# CPU_GPIOA_F.net
KiCad netlist of a schematic drawn in Altium Designer
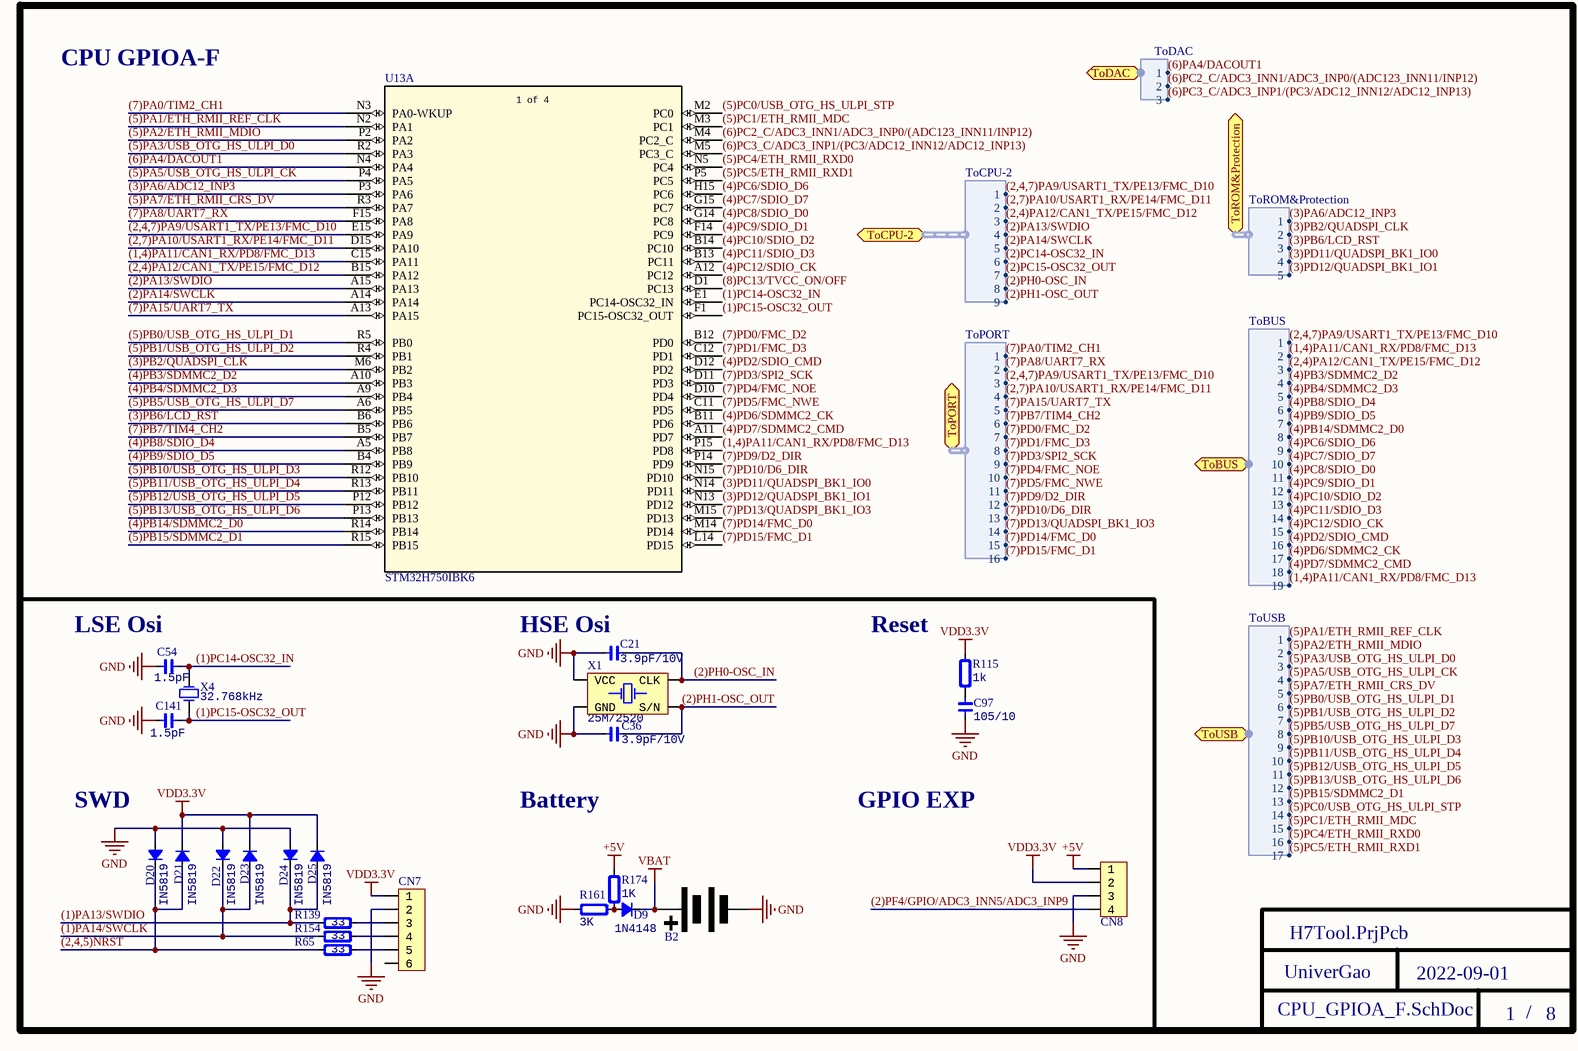
[diagram p0: CPU_GPIOA_F.SchDoc]

(export (version "E")
  (design (tool "Eeschema 10.0.6"))
  (components
    (comp (ref "B2")
      (value "Battery")
      (footprint "PCB_Battery:CR2032-1")
      (libsource (lib "SCH_Battery") (part "Battery"))
    )
    (comp (ref "C21")
      (value "3.9pF/10V")
      (footprint "PCB_PassiveCap:CAP_0603")
      (description "Capacitor")
      (fields (field (name "Comment") "C0603"))
      (libsource (lib "SCH_Passive") (part "Cap_0603"))
    )
    (comp (ref "C36")
      (value "3.9pF/10V")
      (footprint "PCB_PassiveCap:CAP_0603")
      (description "Capacitor")
      (fields (field (name "Comment") "C0603"))
      (libsource (lib "SCH_Passive") (part "Cap_0603"))
    )
    (comp (ref "C54")
      (value "1.5pF")
      (footprint "PCB_PassiveCap:CAP_0603")
      (description "Capacitor")
      (fields (field (name "Comment") "C0603"))
      (libsource (lib "SCH_Passive") (part "Cap_0603"))
    )
    (comp (ref "C97")
      (value "105/10")
      (footprint "PCB_PassiveCap:CAP_0603")
      (description "Capacitor")
      (fields (field (name "Comment") "C0603"))
      (libsource (lib "") (part "Cap_0603_1"))
    )
    (comp (ref "C141")
      (value "1.5pF")
      (footprint "PCB_PassiveCap:CAP_0603")
      (description "Capacitor")
      (fields (field (name "Comment") "C0603"))
      (libsource (lib "SCH_Passive") (part "Cap_0603"))
    )
    (comp (ref "CN7")
      (value "HDR1x6")
      (footprint "PCB_ConnectorHDR:HDR1X6_1.27_180")
      (description "Header")
      (libsource (lib "SCH_ConnectorHDR") (part "HDR1x6_1.27"))
    )
    (comp (ref "CN8")
      (value "HDR1x4")
      (footprint "PCB_ConnectorHDR:HDR1X4_1.27_180")
      (description "Header")
      (libsource (lib "SCH_ConnectorHDR") (part "HDR1x4_1.27"))
    )
    (comp (ref "D9")
      (value "1N4148")
      (footprint "PCB_ActiveDIO:DO-214AC")
      (description "Diode")
      (libsource (lib "SCH_Active") (part "Diode_SMA"))
    )
    (comp (ref "D20")
      (value "~")
      (footprint "PCB_ActiveDIO:SOD-323")
      (description "Diode")
      (fields (field (name "IN5819") "IN5819"))
      (libsource (lib "SCH_Active") (part "Diode_SOD323"))
    )
    (comp (ref "D21")
      (value "~")
      (footprint "PCB_ActiveDIO:SOD-323")
      (description "Diode")
      (fields (field (name "IN5819") "IN5819"))
      (libsource (lib "SCH_Active") (part "Diode_SOD323"))
    )
    (comp (ref "D22")
      (value "~")
      (footprint "PCB_ActiveDIO:SOD-323")
      (description "Diode")
      (fields (field (name "IN5819") "IN5819"))
      (libsource (lib "SCH_Active") (part "Diode_SOD323"))
    )
    (comp (ref "D23")
      (value "~")
      (footprint "PCB_ActiveDIO:SOD-323")
      (description "Diode")
      (fields (field (name "IN5819") "IN5819"))
      (libsource (lib "SCH_Active") (part "Diode_SOD323"))
    )
    (comp (ref "D24")
      (value "~")
      (footprint "PCB_ActiveDIO:SOD-323")
      (description "Diode")
      (fields (field (name "IN5819") "IN5819"))
      (libsource (lib "SCH_Active") (part "Diode_SOD323"))
    )
    (comp (ref "D25")
      (value "~")
      (footprint "PCB_ActiveDIO:SOD-323")
      (description "Diode")
      (fields (field (name "IN5819") "IN5819"))
      (libsource (lib "SCH_Active") (part "Diode_SOD323"))
    )
    (comp (ref "R65")
      (value "33")
      (footprint "PCB_PassiveRes:RES_0603")
      (description "Resistor")
      (fields (field (name "Comment") "R0603"))
      (libsource (lib "SCH_Passive") (part "Res_0603"))
    )
    (comp (ref "R115")
      (value "1k")
      (footprint "PCB_PassiveRes:RES_0603")
      (description "Resistor")
      (fields (field (name "Comment") "R0603"))
      (libsource (lib "SCH_Passive") (part "Res_0603"))
    )
    (comp (ref "R139")
      (value "33")
      (footprint "PCB_PassiveRes:RES_0603")
      (description "Resistor")
      (fields (field (name "Comment") "R0603"))
      (libsource (lib "SCH_Passive") (part "Res_0603"))
    )
    (comp (ref "R154")
      (value "33")
      (footprint "PCB_PassiveRes:RES_0603")
      (description "Resistor")
      (fields (field (name "Comment") "R0603"))
      (libsource (lib "SCH_Passive") (part "Res_0603"))
    )
    (comp (ref "R161")
      (value "3K")
      (footprint "PCB_PassiveRes:RES_0603")
      (description "Resistor")
      (fields (field (name "Comment") "R0603"))
      (libsource (lib "SCH_Passive") (part "Res_0603"))
    )
    (comp (ref "R174")
      (value "1K")
      (footprint "PCB_PassiveRes:RES_0603")
      (description "Resistor")
      (fields (field (name "Comment") "R0603"))
      (libsource (lib "SCH_Passive") (part "Res_0603"))
    )
    (comp (ref "U13")
      (value "STM32H750IBK6")
      (footprint "UFBGA 10X10 P 0.65 176+25")
      (description "No Description Available")
      (fields (field (name "COPYRIGHT") "Copyright (C) 2022 Ultra Librarian. All rights reserved."))
      (libsource (lib "STM32H750IBK6") (part "STM32H750IBK6"))
    )
    (comp (ref "X1")
      (value "25M/2520")
      (footprint "PCB_Oscillator:XT_2520_4")
      (description "Crystal Oscillator")
      (fields (field (name "Comment") "OSC2520"))
      (libsource (lib "SCH_Oscillator") (part "OSC_2520_4P"))
    )
    (comp (ref "X4")
      (value "32.768kHz")
      (footprint "PCB_Oscillator:XT_2012_2")
      (description "Crystal Oscillator")
      (fields (field (name "Comment") "XTAL2012"))
      (libsource (lib "SCH_Oscillator") (part "XTAL_32.768k_2P"))
    )
  )
  (nets
    (net (code "7") (name "+5V") (class "Default")
      (node (ref "CN8") (pin "1") (pinfunction "1_1") (pintype "passive"))
      (node (ref "R174") (pin "2") (pinfunction "2_2") (pintype "passive"))
    )
    (net (code "8") (name "/(1)PA13{slash}SWDIO") (class "Default")
      (node (ref "D24") (pin "2") (pinfunction "K_2") (pintype "passive"))
      (node (ref "D25") (pin "1") (pinfunction "A_1") (pintype "passive"))
      (node (ref "R139") (pin "1") (pinfunction "1_1") (pintype "passive"))
    )
    (net (code "9") (name "/(1)PA14{slash}SWCLK") (class "Default")
      (node (ref "D22") (pin "2") (pinfunction "K_2") (pintype "passive"))
      (node (ref "D23") (pin "1") (pinfunction "A_1") (pintype "passive"))
      (node (ref "R154") (pin "1") (pinfunction "1_1") (pintype "passive"))
    )
    (net (code "10") (name "/(1)PC14-OSC32_IN") (class "Default")
      (node (ref "C54") (pin "2") (pinfunction "2_2") (pintype "passive"))
      (node (ref "U13") (pin "E1") (pinfunction "PC14-OSC32_IN_E1") (pintype "bidirectional"))
      (node (ref "X4") (pin "2") (pinfunction "OSC2_2") (pintype "passive"))
    )
    (net (code "11") (name "/(1)PC15-OSC32_OUT") (class "Default")
      (node (ref "C141") (pin "2") (pinfunction "2_2") (pintype "passive"))
      (node (ref "U13") (pin "F1") (pinfunction "PC15-OSC32_OUT_F1") (pintype "bidirectional"))
      (node (ref "X4") (pin "1") (pinfunction "OSC1_1") (pintype "passive"))
    )
    (net (code "12") (name "/(1,4)PA11{slash}CAN1_RX{slash}PD8{slash}FMC_D13") (class "Default")
      (node (ref "U13") (pin "C15") (pinfunction "PA11_C15") (pintype "bidirectional"))
      (node (ref "U13") (pin "P15") (pinfunction "PD8_P15") (pintype "bidirectional"))
    )
    (net (code "13") (name "/(2)PA13{slash}SWDIO") (class "Default")
      (node (ref "U13") (pin "A15") (pinfunction "PA13_A15") (pintype "bidirectional"))
    )
    (net (code "14") (name "/(2)PA14{slash}SWCLK") (class "Default")
      (node (ref "U13") (pin "A14") (pinfunction "PA14_A14") (pintype "bidirectional"))
    )
    (net (code "17") (name "/(2)PF4{slash}GPIO{slash}ADC3_INN5{slash}ADC3_INP9") (class "Default")
      (node (ref "CN8") (pin "4") (pinfunction "4_4") (pintype "passive"))
    )
    (net (code "18") (name "/(2)PH0-OSC_IN") (class "Default")
      (node (ref "C21") (pin "2") (pinfunction "2_2") (pintype "passive"))
      (node (ref "X1") (pin "3") (pinfunction "CLK_3") (pintype "passive"))
    )
    (net (code "19") (name "/(2)PH1-OSC_OUT") (class "Default")
      (node (ref "C36") (pin "2") (pinfunction "2_2") (pintype "passive"))
      (node (ref "X1") (pin "1") (pinfunction "S/N_1") (pintype "passive"))
    )
    (net (code "20") (name "/(2,4)PA12{slash}CAN1_TX{slash}PE15{slash}FMC_D12") (class "Default")
      (node (ref "U13") (pin "B15") (pinfunction "PA12_B15") (pintype "bidirectional"))
    )
    (net (code "21") (name "/(2,4,5)NRST") (class "Default")
      (node (ref "D20") (pin "2") (pinfunction "K_2") (pintype "passive"))
      (node (ref "D21") (pin "1") (pinfunction "A_1") (pintype "passive"))
      (node (ref "R65") (pin "1") (pinfunction "1_1") (pintype "passive"))
    )
    (net (code "22") (name "/(2,4,7)PA9{slash}USART1_TX{slash}PE13{slash}FMC_D10") (class "Default")
      (node (ref "U13") (pin "E15") (pinfunction "PA9_E15") (pintype "bidirectional"))
    )
    (net (code "23") (name "/(2,7)PA10{slash}USART1_RX{slash}PE14{slash}FMC_D11") (class "Default")
      (node (ref "U13") (pin "D15") (pinfunction "PA10_D15") (pintype "bidirectional"))
    )
    (net (code "24") (name "/(3)PA6{slash}ADC12_INP3") (class "Default")
      (node (ref "U13") (pin "P3") (pinfunction "PA6_P3") (pintype "bidirectional"))
    )
    (net (code "25") (name "/(3)PB2{slash}QUADSPI_CLK") (class "Default")
      (node (ref "U13") (pin "M6") (pinfunction "PB2_M6") (pintype "bidirectional"))
    )
    (net (code "26") (name "/(3)PB6{slash}LCD_RST") (class "Default")
      (node (ref "U13") (pin "B6") (pinfunction "PB6_B6") (pintype "bidirectional"))
    )
    (net (code "27") (name "/(3)PD11{slash}QUADSPI_BK1_IO0") (class "Default")
      (node (ref "U13") (pin "N14") (pinfunction "PD11_N14") (pintype "bidirectional"))
    )
    (net (code "28") (name "/(3)PD12{slash}QUADSPI_BK1_IO1") (class "Default")
      (node (ref "U13") (pin "N13") (pinfunction "PD12_N13") (pintype "bidirectional"))
    )
    (net (code "29") (name "/(4)PB3{slash}SDMMC2_D2") (class "Default")
      (node (ref "U13") (pin "A10") (pinfunction "PB3_A10") (pintype "bidirectional"))
    )
    (net (code "30") (name "/(4)PB4{slash}SDMMC2_D3") (class "Default")
      (node (ref "U13") (pin "A9") (pinfunction "PB4_A9") (pintype "bidirectional"))
    )
    (net (code "31") (name "/(4)PB8{slash}SDIO_D4") (class "Default")
      (node (ref "U13") (pin "A5") (pinfunction "PB8_A5") (pintype "bidirectional"))
    )
    (net (code "32") (name "/(4)PB9{slash}SDIO_D5") (class "Default")
      (node (ref "U13") (pin "B4") (pinfunction "PB9_B4") (pintype "bidirectional"))
    )
    (net (code "33") (name "/(4)PB14{slash}SDMMC2_D0") (class "Default")
      (node (ref "U13") (pin "R14") (pinfunction "PB14_R14") (pintype "bidirectional"))
    )
    (net (code "34") (name "/(4)PC6{slash}SDIO_D6") (class "Default")
      (node (ref "U13") (pin "H15") (pinfunction "PC6_H15") (pintype "bidirectional"))
    )
    (net (code "35") (name "/(4)PC7{slash}SDIO_D7") (class "Default")
      (node (ref "U13") (pin "G15") (pinfunction "PC7_G15") (pintype "bidirectional"))
    )
    (net (code "36") (name "/(4)PC8{slash}SDIO_D0") (class "Default")
      (node (ref "U13") (pin "G14") (pinfunction "PC8_G14") (pintype "bidirectional"))
    )
    (net (code "37") (name "/(4)PC9{slash}SDIO_D1") (class "Default")
      (node (ref "U13") (pin "F14") (pinfunction "PC9_F14") (pintype "bidirectional"))
    )
    (net (code "38") (name "/(4)PC10{slash}SDIO_D2") (class "Default")
      (node (ref "U13") (pin "B14") (pinfunction "PC10_B14") (pintype "bidirectional"))
    )
    (net (code "39") (name "/(4)PC11{slash}SDIO_D3") (class "Default")
      (node (ref "U13") (pin "B13") (pinfunction "PC11_B13") (pintype "bidirectional"))
    )
    (net (code "40") (name "/(4)PC12{slash}SDIO_CK") (class "Default")
      (node (ref "U13") (pin "A12") (pinfunction "PC12_A12") (pintype "bidirectional"))
    )
    (net (code "41") (name "/(4)PD2{slash}SDIO_CMD") (class "Default")
      (node (ref "U13") (pin "D12") (pinfunction "PD2_D12") (pintype "bidirectional"))
    )
    (net (code "42") (name "/(4)PD6{slash}SDMMC2_CK") (class "Default")
      (node (ref "U13") (pin "B11") (pinfunction "PD6_B11") (pintype "bidirectional"))
    )
    (net (code "43") (name "/(4)PD7{slash}SDMMC2_CMD") (class "Default")
      (node (ref "U13") (pin "A11") (pinfunction "PD7_A11") (pintype "bidirectional"))
    )
    (net (code "44") (name "/(5)PA1{slash}ETH_RMII_REF_CLK") (class "Default")
      (node (ref "U13") (pin "N2") (pinfunction "PA1_N2") (pintype "bidirectional"))
    )
    (net (code "45") (name "/(5)PA2{slash}ETH_RMII_MDIO") (class "Default")
      (node (ref "U13") (pin "P2") (pinfunction "PA2_P2") (pintype "bidirectional"))
    )
    (net (code "46") (name "/(5)PA3{slash}USB_OTG_HS_ULPI_D0") (class "Default")
      (node (ref "U13") (pin "R2") (pinfunction "PA3_R2") (pintype "bidirectional"))
    )
    (net (code "47") (name "/(5)PA5{slash}USB_OTG_HS_ULPI_CK") (class "Default")
      (node (ref "U13") (pin "P4") (pinfunction "PA5_P4") (pintype "bidirectional"))
    )
    (net (code "48") (name "/(5)PA7{slash}ETH_RMII_CRS_DV") (class "Default")
      (node (ref "U13") (pin "R3") (pinfunction "PA7_R3") (pintype "bidirectional"))
    )
    (net (code "49") (name "/(5)PB0{slash}USB_OTG_HS_ULPI_D1") (class "Default")
      (node (ref "U13") (pin "R5") (pinfunction "PB0_R5") (pintype "bidirectional"))
    )
    (net (code "50") (name "/(5)PB1{slash}USB_OTG_HS_ULPI_D2") (class "Default")
      (node (ref "U13") (pin "R4") (pinfunction "PB1_R4") (pintype "bidirectional"))
    )
    (net (code "51") (name "/(5)PB5{slash}USB_OTG_HS_ULPI_D7") (class "Default")
      (node (ref "U13") (pin "A6") (pinfunction "PB5_A6") (pintype "bidirectional"))
    )
    (net (code "52") (name "/(5)PB10{slash}USB_OTG_HS_ULPI_D3") (class "Default")
      (node (ref "U13") (pin "R12") (pinfunction "PB10_R12") (pintype "bidirectional"))
    )
    (net (code "53") (name "/(5)PB11{slash}USB_OTG_HS_ULPI_D4") (class "Default")
      (node (ref "U13") (pin "R13") (pinfunction "PB11_R13") (pintype "bidirectional"))
    )
    (net (code "54") (name "/(5)PB12{slash}USB_OTG_HS_ULPI_D5") (class "Default")
      (node (ref "U13") (pin "P12") (pinfunction "PB12_P12") (pintype "bidirectional"))
    )
    (net (code "55") (name "/(5)PB13{slash}USB_OTG_HS_ULPI_D6") (class "Default")
      (node (ref "U13") (pin "P13") (pinfunction "PB13_P13") (pintype "bidirectional"))
    )
    (net (code "56") (name "/(5)PB15{slash}SDMMC2_D1") (class "Default")
      (node (ref "U13") (pin "R15") (pinfunction "PB15_R15") (pintype "bidirectional"))
    )
    (net (code "57") (name "/(5)PC0{slash}USB_OTG_HS_ULPI_STP") (class "Default")
      (node (ref "U13") (pin "M2") (pinfunction "PC0_M2") (pintype "bidirectional"))
    )
    (net (code "58") (name "/(5)PC1{slash}ETH_RMII_MDC") (class "Default")
      (node (ref "U13") (pin "M3") (pinfunction "PC1_M3") (pintype "bidirectional"))
    )
    (net (code "59") (name "/(5)PC4{slash}ETH_RMII_RXD0") (class "Default")
      (node (ref "U13") (pin "N5") (pinfunction "PC4_N5") (pintype "bidirectional"))
    )
    (net (code "60") (name "/(5)PC5{slash}ETH_RMII_RXD1") (class "Default")
      (node (ref "U13") (pin "P5") (pinfunction "PC5_P5") (pintype "bidirectional"))
    )
    (net (code "61") (name "/(6)PA4{slash}DACOUT1") (class "Default")
      (node (ref "U13") (pin "N4") (pinfunction "PA4_N4") (pintype "bidirectional"))
    )
    (net (code "62") (name "/(6)PC2_C{slash}ADC3_INN1{slash}ADC3_INP0{slash}(ADC123_INN11{slash}INP12)") (class "Default")
      (node (ref "U13") (pin "M4") (pinfunction "PC2_C_M4") (pintype "bidirectional"))
    )
    (net (code "63") (name "/(6)PC3_C{slash}ADC3_INP1{slash}(PC3{slash}ADC12_INN12{slash}ADC12_INP13)") (class "Default")
      (node (ref "U13") (pin "M5") (pinfunction "PC3_C_M5") (pintype "bidirectional"))
    )
    (net (code "64") (name "/(7)PA0{slash}TIM2_CH1") (class "Default")
      (node (ref "U13") (pin "N3") (pinfunction "PA0-WKUP_N3") (pintype "bidirectional"))
    )
    (net (code "65") (name "/(7)PA8{slash}UART7_RX") (class "Default")
      (node (ref "U13") (pin "F15") (pinfunction "PA8_F15") (pintype "bidirectional"))
    )
    (net (code "66") (name "/(7)PA15{slash}UART7_TX") (class "Default")
      (node (ref "U13") (pin "A13") (pinfunction "PA15_A13") (pintype "bidirectional"))
    )
    (net (code "67") (name "/(7)PB7{slash}TIM4_CH2") (class "Default")
      (node (ref "U13") (pin "B5") (pinfunction "PB7_B5") (pintype "bidirectional"))
    )
    (net (code "68") (name "/(7)PD0{slash}FMC_D2") (class "Default")
      (node (ref "U13") (pin "B12") (pinfunction "PD0_B12") (pintype "bidirectional"))
    )
    (net (code "69") (name "/(7)PD1{slash}FMC_D3") (class "Default")
      (node (ref "U13") (pin "C12") (pinfunction "PD1_C12") (pintype "bidirectional"))
    )
    (net (code "70") (name "/(7)PD3{slash}SPI2_SCK") (class "Default")
      (node (ref "U13") (pin "D11") (pinfunction "PD3_D11") (pintype "bidirectional"))
    )
    (net (code "71") (name "/(7)PD4{slash}FMC_NOE") (class "Default")
      (node (ref "U13") (pin "D10") (pinfunction "PD4_D10") (pintype "bidirectional"))
    )
    (net (code "72") (name "/(7)PD5{slash}FMC_NWE") (class "Default")
      (node (ref "U13") (pin "C11") (pinfunction "PD5_C11") (pintype "bidirectional"))
    )
    (net (code "73") (name "/(7)PD9{slash}D2_DIR") (class "Default")
      (node (ref "U13") (pin "P14") (pinfunction "PD9_P14") (pintype "bidirectional"))
    )
    (net (code "74") (name "/(7)PD10{slash}D6_DIR") (class "Default")
      (node (ref "U13") (pin "N15") (pinfunction "PD10_N15") (pintype "bidirectional"))
    )
    (net (code "75") (name "/(7)PD13{slash}QUADSPI_BK1_IO3") (class "Default")
      (node (ref "U13") (pin "M15") (pinfunction "PD13_M15") (pintype "bidirectional"))
    )
    (net (code "76") (name "/(7)PD14{slash}FMC_D0") (class "Default")
      (node (ref "U13") (pin "M14") (pinfunction "PD14_M14") (pintype "bidirectional"))
    )
    (net (code "77") (name "/(7)PD15{slash}FMC_D1") (class "Default")
      (node (ref "U13") (pin "L14") (pinfunction "PD15_L14") (pintype "bidirectional"))
    )
    (net (code "78") (name "/(8)PC13{slash}TVCC_ON{slash}OFF") (class "Default")
      (node (ref "U13") (pin "D1") (pinfunction "PC13_D1") (pintype "bidirectional"))
    )
    (net (code "85") (name "GND") (class "Default")
      (node (ref "B2") (pin "1") (pinfunction "-_1") (pintype "passive"))
      (node (ref "C141") (pin "1") (pinfunction "1_1") (pintype "passive"))
      (node (ref "C21") (pin "1") (pinfunction "1_1") (pintype "passive"))
      (node (ref "C36") (pin "1") (pinfunction "1_1") (pintype "passive"))
      (node (ref "C54") (pin "1") (pinfunction "1_1") (pintype "passive"))
      (node (ref "C97") (pin "1") (pinfunction "1_1") (pintype "passive"))
      (node (ref "CN7") (pin "2") (pinfunction "2_2") (pintype "passive"))
      (node (ref "CN8") (pin "3") (pinfunction "3_3") (pintype "passive"))
      (node (ref "D20") (pin "1") (pinfunction "A_1") (pintype "passive"))
      (node (ref "D22") (pin "1") (pinfunction "A_1") (pintype "passive"))
      (node (ref "D24") (pin "1") (pinfunction "A_1") (pintype "passive"))
      (node (ref "R161") (pin "2") (pinfunction "2_2") (pintype "passive"))
      (node (ref "X1") (pin "2") (pinfunction "GND_2") (pintype "passive"))
      (node (ref "X1") (pin "4") (pinfunction "VCC_4") (pintype "passive"))
    )
    (net (code "86") (name "Net-(C97-Pad2)") (class "Default")
      (node (ref "C97") (pin "2") (pinfunction "2_2") (pintype "passive"))
      (node (ref "R115") (pin "1") (pinfunction "1_1") (pintype "passive"))
    )
    (net (code "87") (name "Net-(CN7-Pad3)") (class "Default")
      (node (ref "CN7") (pin "3") (pinfunction "3_3") (pintype "passive"))
      (node (ref "R139") (pin "2") (pinfunction "2_2") (pintype "passive"))
    )
    (net (code "88") (name "Net-(CN7-Pad4)") (class "Default")
      (node (ref "CN7") (pin "4") (pinfunction "4_4") (pintype "passive"))
      (node (ref "R154") (pin "2") (pinfunction "2_2") (pintype "passive"))
    )
    (net (code "89") (name "Net-(CN7-Pad5)") (class "Default")
      (node (ref "CN7") (pin "5") (pinfunction "5_5") (pintype "passive"))
      (node (ref "R65") (pin "2") (pinfunction "2_2") (pintype "passive"))
    )
    (net (code "90") (name "Net-(D9-A)") (class "Default")
      (node (ref "D9") (pin "1") (pinfunction "A_1") (pintype "passive"))
      (node (ref "R161") (pin "1") (pinfunction "1_1") (pintype "passive"))
      (node (ref "R174") (pin "1") (pinfunction "1_1") (pintype "passive"))
    )
    (net (code "91") (name "VBAT") (class "Default")
      (node (ref "B2") (pin "2") (pinfunction "+_2") (pintype "passive"))
      (node (ref "D9") (pin "2") (pinfunction "K_2") (pintype "passive"))
    )
    (net (code "92") (name "VDD3.3V") (class "Default")
      (node (ref "CN7") (pin "1") (pinfunction "1_1") (pintype "passive"))
      (node (ref "CN8") (pin "2") (pinfunction "2_2") (pintype "passive"))
      (node (ref "D21") (pin "2") (pinfunction "K_2") (pintype "passive"))
      (node (ref "D23") (pin "2") (pinfunction "K_2") (pintype "passive"))
      (node (ref "D25") (pin "2") (pinfunction "K_2") (pintype "passive"))
      (node (ref "R115") (pin "2") (pinfunction "2_2") (pintype "passive"))
    )
    (net (code "93") (name "unconnected-(CN7-Pad6)") (class "Default")
      (node (ref "CN7") (pin "6") (pinfunction "6_6") (pintype "passive"))
    )
  )
)
